# CATS-Vega-Radio_MCU.net
KiCad netlist of a schematic drawn in Altium Designer
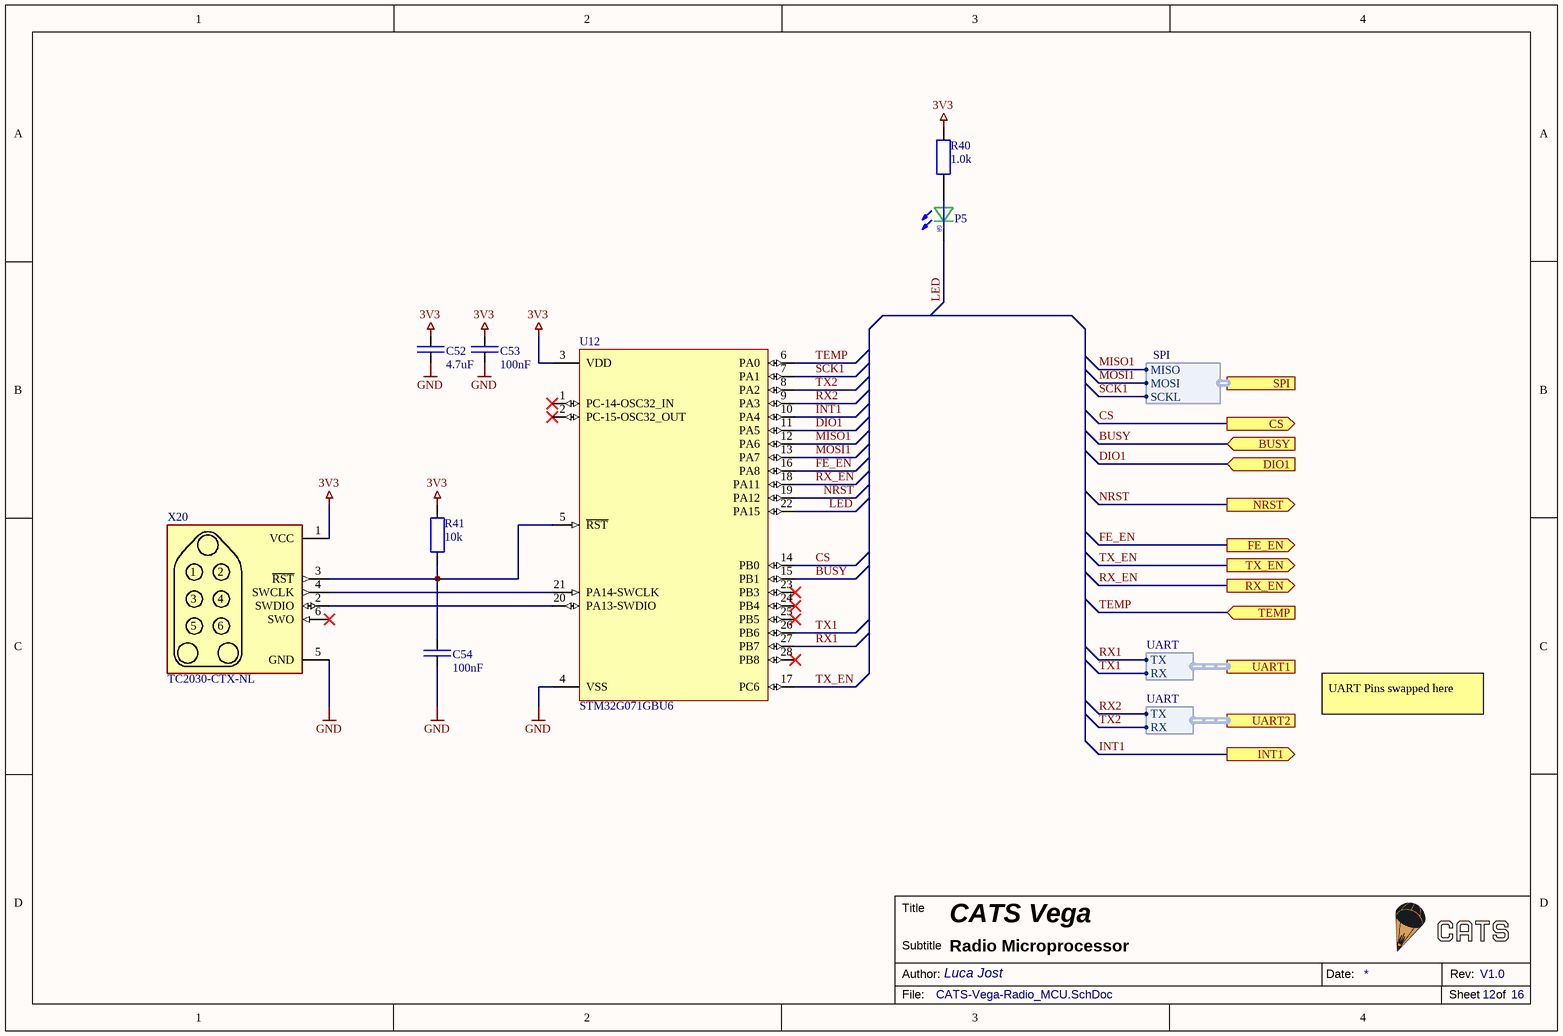
[diagram p0: CATS-Vega-Radio_MCU.SchDoc]

(export (version "E")
  (design (tool "Eeschema 10.0.6"))
  (components
    (comp (ref "C52")
      (value "4.7uF")
      (footprint "SMD Keramikkondensator 0603")
      (description "SMD Ceramic Capacitor E6")
      (libsource (lib "CATS-EUROC") (part "E6 - 4.7uF"))
    )
    (comp (ref "C53")
      (value "100nF")
      (footprint "SMD Keramikkondensator 0603")
      (description "SMD Ceramic Capacitor E6")
      (libsource (lib "CATS-EUROC") (part "E6 - 100nF"))
    )
    (comp (ref "C54")
      (value "100nF")
      (footprint "SMD Keramikkondensator 0603")
      (description "SMD Ceramic Capacitor E6")
      (libsource (lib "CATS-EUROC") (part "E6 - 100nF"))
    )
    (comp (ref "P5")
      (value "LED")
      (footprint "SMD LED 0603")
      (description "Color LED")
      (libsource (lib "Diodes") (part "LED"))
    )
    (comp (ref "R40")
      (value "1.0k")
      (footprint "SMD Widerstand 0603")
      (description "SMD Chip Resistor E24")
      (libsource (lib "CATS-EUROC") (part "E24 - 1.0k"))
    )
    (comp (ref "R41")
      (value "10k")
      (footprint "SMD Widerstand 0603")
      (description "SMD Chip Resistor E24")
      (libsource (lib "CATS-EUROC") (part "E24 - 10k"))
    )
    (comp (ref "U12")
      (value "STM32G071GBU6")
      (footprint "SMD IC QFN-28 4x4 0.5 Pitch")
      (description "ARM® Cortex®-M0+ series Microcontroller IC 32-Bit 64MHz 128KB (128K x 8) FLASH 28-UFQFPN (4x4)")
      (libsource (lib "Microcontrollers") (part "STM32G071GBU6"))
    )
    (comp (ref "X20")
      (value "TC2030-CTX-NL")
      (footprint "SMD Connector TC2030")
      (description "Tag-Connect for ARM-Cortex (6-Pin)")
      (libsource (lib "Connectors") (part "TC2030-CTX-NL"))
    )
  )
  (nets
    (net (code "3") (name "/BUSY") (class "Default")
      (node (ref "U12") (pin "15") (pinfunction "PB1_15") (pintype "bidirectional"))
    )
    (net (code "4") (name "/CS") (class "Default")
      (node (ref "U12") (pin "14") (pinfunction "PB0_14") (pintype "bidirectional"))
    )
    (net (code "5") (name "/DIO1") (class "Default")
      (node (ref "U12") (pin "11") (pinfunction "PA5_11") (pintype "bidirectional"))
    )
    (net (code "6") (name "/FE_EN") (class "Default")
      (node (ref "U12") (pin "16") (pinfunction "PA8_16") (pintype "bidirectional"))
    )
    (net (code "7") (name "/INT1") (class "Default")
      (node (ref "U12") (pin "10") (pinfunction "PA4_10") (pintype "bidirectional"))
    )
    (net (code "8") (name "/LED") (class "Default")
      (node (ref "P5") (pin "K") (pinfunction "K_K") (pintype "passive"))
      (node (ref "U12") (pin "22") (pinfunction "PA15_22") (pintype "bidirectional"))
    )
    (net (code "9") (name "/MISO1") (class "Default")
      (node (ref "U12") (pin "12") (pinfunction "PA6_12") (pintype "bidirectional"))
    )
    (net (code "10") (name "/MOSI1") (class "Default")
      (node (ref "U12") (pin "13") (pinfunction "PA7_13") (pintype "bidirectional"))
    )
    (net (code "11") (name "/NRST") (class "Default")
      (node (ref "U12") (pin "19") (pinfunction "PA12_19") (pintype "bidirectional"))
    )
    (net (code "12") (name "/RX1") (class "Default")
      (node (ref "U12") (pin "27") (pinfunction "PB7_27") (pintype "bidirectional"))
    )
    (net (code "13") (name "/RX2") (class "Default")
      (node (ref "U12") (pin "9") (pinfunction "PA3_9") (pintype "bidirectional"))
    )
    (net (code "14") (name "/RX_EN") (class "Default")
      (node (ref "U12") (pin "18") (pinfunction "PA11_18") (pintype "bidirectional"))
    )
    (net (code "15") (name "/SCK1") (class "Default")
      (node (ref "U12") (pin "7") (pinfunction "PA1_7") (pintype "bidirectional"))
    )
    (net (code "16") (name "/TEMP") (class "Default")
      (node (ref "U12") (pin "6") (pinfunction "PA0_6") (pintype "bidirectional"))
    )
    (net (code "17") (name "/TX1") (class "Default")
      (node (ref "U12") (pin "26") (pinfunction "PB6_26") (pintype "bidirectional"))
    )
    (net (code "18") (name "/TX2") (class "Default")
      (node (ref "U12") (pin "8") (pinfunction "PA2_8") (pintype "bidirectional"))
    )
    (net (code "19") (name "/TX_EN") (class "Default")
      (node (ref "U12") (pin "17") (pinfunction "PC6_17") (pintype "bidirectional"))
    )
    (net (code "22") (name "3V3") (class "Default")
      (node (ref "C52") (pin "2") (pinfunction "2_2") (pintype "passive"))
      (node (ref "C53") (pin "2") (pinfunction "2_2") (pintype "passive"))
      (node (ref "R40") (pin "2") (pinfunction "2_2") (pintype "passive"))
      (node (ref "R41") (pin "2") (pinfunction "2_2") (pintype "passive"))
      (node (ref "U12") (pin "3") (pinfunction "VDD_3") (pintype "passive"))
      (node (ref "X20") (pin "1") (pinfunction "VCC_1") (pintype "power_in"))
    )
    (net (code "23") (name "GND") (class "Default")
      (node (ref "C52") (pin "1") (pinfunction "1_1") (pintype "passive"))
      (node (ref "C53") (pin "1") (pinfunction "1_1") (pintype "passive"))
      (node (ref "C54") (pin "1") (pinfunction "1_1") (pintype "passive"))
      (node (ref "U12") (pin "4") (pinfunction "VSS_4") (pintype "passive"))
      (node (ref "X20") (pin "5") (pinfunction "GND_5") (pintype "power_in"))
    )
    (net (code "24") (name "Net-(P5-PadA)") (class "Default")
      (node (ref "P5") (pin "A") (pinfunction "A_A") (pintype "passive"))
      (node (ref "R40") (pin "1") (pinfunction "1_1") (pintype "passive"))
    )
    (net (code "25") (name "Net-(U12-PA13-SWDIO)") (class "Default")
      (node (ref "U12") (pin "20") (pinfunction "PA13-SWDIO_20") (pintype "bidirectional"))
      (node (ref "X20") (pin "2") (pinfunction "SWDIO_2") (pintype "bidirectional"))
    )
    (net (code "26") (name "Net-(U12-PA14-SWCLK)") (class "Default")
      (node (ref "U12") (pin "21") (pinfunction "PA14-SWCLK_21") (pintype "input"))
      (node (ref "X20") (pin "4") (pinfunction "SWCLK_4") (pintype "output"))
    )
    (net (code "27") (name "Net-(U12-~{RST})") (class "Default")
      (node (ref "C54") (pin "2") (pinfunction "2_2") (pintype "passive"))
      (node (ref "R41") (pin "1") (pinfunction "1_1") (pintype "passive"))
      (node (ref "U12") (pin "5") (pinfunction "~{RST}_5") (pintype "input"))
      (node (ref "X20") (pin "3") (pinfunction "~{RST}_3") (pintype "output"))
    )
    (net (code "28") (name "unconnected-(U12-PB3-Pad23)") (class "Default")
      (node (ref "U12") (pin "23") (pinfunction "PB3_23") (pintype "bidirectional+no_connect"))
    )
    (net (code "29") (name "unconnected-(U12-PB4-Pad24)") (class "Default")
      (node (ref "U12") (pin "24") (pinfunction "PB4_24") (pintype "bidirectional+no_connect"))
    )
    (net (code "30") (name "unconnected-(U12-PB5-Pad25)") (class "Default")
      (node (ref "U12") (pin "25") (pinfunction "PB5_25") (pintype "bidirectional+no_connect"))
    )
    (net (code "31") (name "unconnected-(U12-PB8-Pad28)") (class "Default")
      (node (ref "U12") (pin "28") (pinfunction "PB8_28") (pintype "bidirectional+no_connect"))
    )
    (net (code "32") (name "unconnected-(U12-PC-14-OSC32_IN-Pad1)") (class "Default")
      (node (ref "U12") (pin "1") (pinfunction "PC-14-OSC32_IN_1") (pintype "bidirectional+no_connect"))
    )
    (net (code "33") (name "unconnected-(U12-PC-15-OSC32_OUT-Pad2)") (class "Default")
      (node (ref "U12") (pin "2") (pinfunction "PC-15-OSC32_OUT_2") (pintype "bidirectional+no_connect"))
    )
    (net (code "34") (name "unconnected-(X20-SWO-Pad6)") (class "Default")
      (node (ref "X20") (pin "6") (pinfunction "SWO_6") (pintype "input+no_connect"))
    )
  )
)
